# zumo_uni_i2c_01.net
KiCad netlist of a schematic drawn in EAGLE
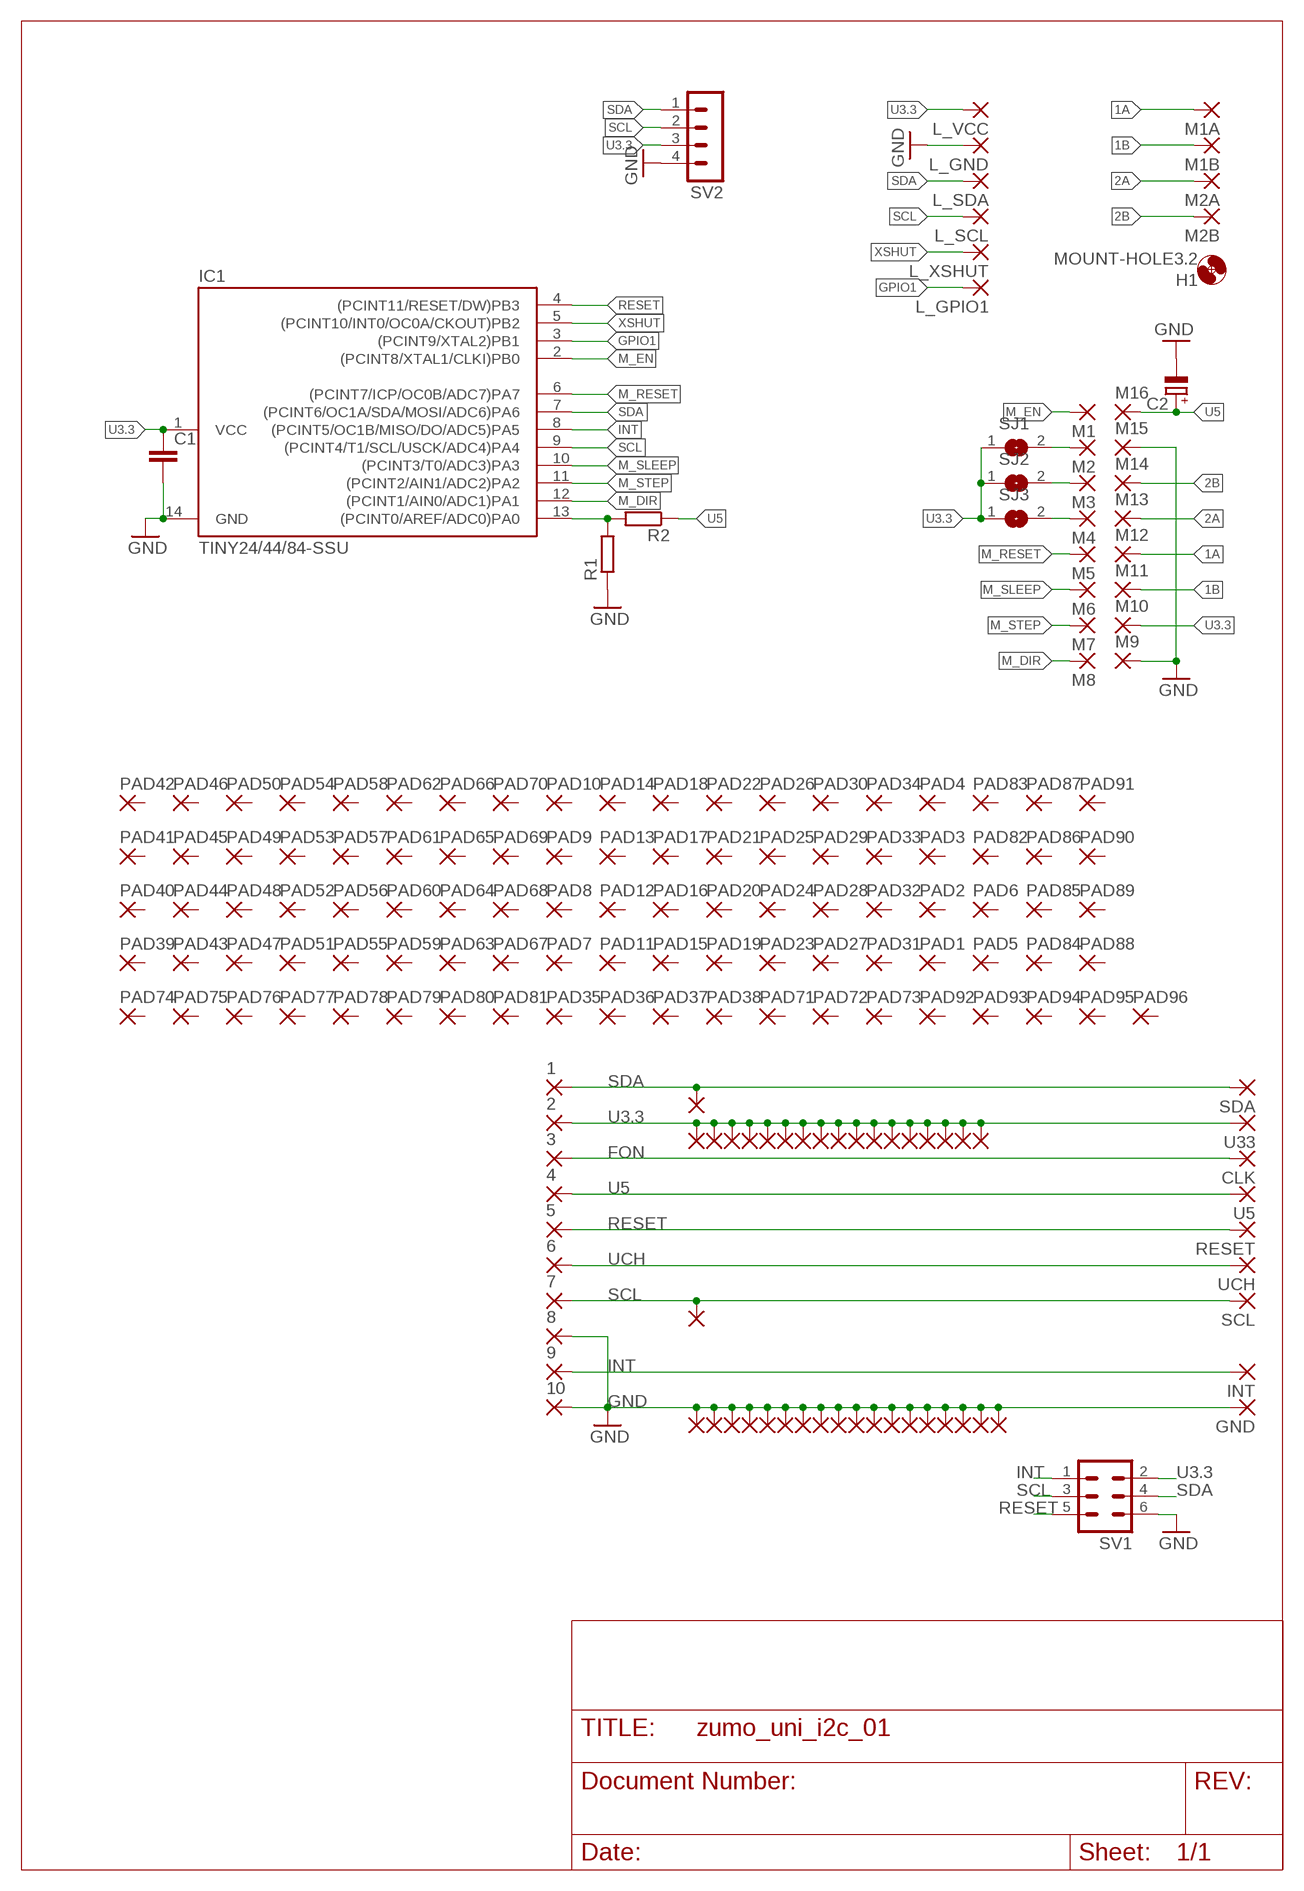
[diagram p0: schematic, sheet 1]

(export (version "E")
  (design (tool "Eeschema 10.0.6"))
  (components
    (comp (ref "1")
      (value "SMD2")
      (footprint "eagle-import:SMD1,27-2,54")
      (libsource (lib "eagle-import") (part "SMD2"))
    )
    (comp (ref "2")
      (value "SMD2")
      (footprint "eagle-import:SMD1,27-2,54")
      (libsource (lib "eagle-import") (part "SMD2"))
    )
    (comp (ref "3")
      (value "SMD2")
      (footprint "eagle-import:SMD1,27-2,54")
      (libsource (lib "eagle-import") (part "SMD2"))
    )
    (comp (ref "4")
      (value "SMD2")
      (footprint "eagle-import:SMD1,27-2,54")
      (libsource (lib "eagle-import") (part "SMD2"))
    )
    (comp (ref "5")
      (value "SMD2")
      (footprint "eagle-import:SMD1,27-2,54")
      (libsource (lib "eagle-import") (part "SMD2"))
    )
    (comp (ref "6")
      (value "SMD2")
      (footprint "eagle-import:SMD1,27-2,54")
      (libsource (lib "eagle-import") (part "SMD2"))
    )
    (comp (ref "7")
      (value "SMD2")
      (footprint "eagle-import:SMD1,27-2,54")
      (libsource (lib "eagle-import") (part "SMD2"))
    )
    (comp (ref "8")
      (value "SMD2")
      (footprint "eagle-import:SMD1,27-2,54")
      (libsource (lib "eagle-import") (part "SMD2"))
    )
    (comp (ref "9")
      (value "SMD2")
      (footprint "eagle-import:SMD1,27-2,54")
      (libsource (lib "eagle-import") (part "SMD2"))
    )
    (comp (ref "10")
      (value "SMD2")
      (footprint "eagle-import:SMD1,27-2,54")
      (libsource (lib "eagle-import") (part "SMD2"))
    )
    (comp (ref "C1")
      (value "C-EUC0805")
      (footprint "eagle-import:C0805")
      (libsource (lib "eagle-import") (part "C-EUC0805"))
    )
    (comp (ref "C2")
      (value "CPOL-EUSMCC")
      (footprint "eagle-import:SMC_C")
      (libsource (lib "eagle-import") (part "CPOL-EUSMCC"))
    )
    (comp (ref "CLK")
      (value "1,6/0,9")
      (footprint "eagle-import:1,6_0,9")
      (libsource (lib "eagle-import") (part "1,6/0,9"))
    )
    (comp (ref "GND")
      (value "1,6/0,9")
      (footprint "eagle-import:1,6_0,9")
      (libsource (lib "eagle-import") (part "1,6/0,9"))
    )
    (comp (ref "H1")
      (value "MOUNT-HOLE3.2")
      (footprint "eagle-import:3,2")
      (libsource (lib "eagle-import") (part "MOUNT-HOLE3.2"))
    )
    (comp (ref "IC1")
      (value "TINY24/44/84-SSU")
      (footprint "eagle-import:SOIC14")
      (libsource (lib "eagle-import") (part "TINY24/44/84-SSU"))
    )
    (comp (ref "INT")
      (value "1,6/0,9")
      (footprint "eagle-import:1,6_0,9")
      (libsource (lib "eagle-import") (part "1,6/0,9"))
    )
    (comp (ref "L_GND")
      (value "1,6/0,8")
      (footprint "eagle-import:1,6_0,8")
      (libsource (lib "eagle-import") (part "1,6/0,8"))
    )
    (comp (ref "L_GPIO1")
      (value "1,6/0,8")
      (footprint "eagle-import:1,6_0,8")
      (libsource (lib "eagle-import") (part "1,6/0,8"))
    )
    (comp (ref "L_SCL")
      (value "1,6/0,8")
      (footprint "eagle-import:1,6_0,8")
      (libsource (lib "eagle-import") (part "1,6/0,8"))
    )
    (comp (ref "L_SDA")
      (value "1,6/0,8")
      (footprint "eagle-import:1,6_0,8")
      (libsource (lib "eagle-import") (part "1,6/0,8"))
    )
    (comp (ref "L_VCC")
      (value "1,6/0,8")
      (footprint "eagle-import:1,6_0,8")
      (libsource (lib "eagle-import") (part "1,6/0,8"))
    )
    (comp (ref "L_XSHUT")
      (value "1,6/0,8")
      (footprint "eagle-import:1,6_0,8")
      (libsource (lib "eagle-import") (part "1,6/0,8"))
    )
    (comp (ref "M1")
      (value "1,6/0,9")
      (footprint "eagle-import:1,6_0,9")
      (libsource (lib "eagle-import") (part "1,6/0,9"))
    )
    (comp (ref "M1A")
      (value "1,6/0,8")
      (footprint "eagle-import:1,6_0,8")
      (libsource (lib "eagle-import") (part "1,6/0,8"))
    )
    (comp (ref "M1B")
      (value "1,6/0,8")
      (footprint "eagle-import:1,6_0,8")
      (libsource (lib "eagle-import") (part "1,6/0,8"))
    )
    (comp (ref "M2")
      (value "1,6/0,9")
      (footprint "eagle-import:1,6_0,9")
      (libsource (lib "eagle-import") (part "1,6/0,9"))
    )
    (comp (ref "M2A")
      (value "1,6/0,8")
      (footprint "eagle-import:1,6_0,8")
      (libsource (lib "eagle-import") (part "1,6/0,8"))
    )
    (comp (ref "M2B")
      (value "1,6/0,8")
      (footprint "eagle-import:1,6_0,8")
      (libsource (lib "eagle-import") (part "1,6/0,8"))
    )
    (comp (ref "M3")
      (value "1,6/0,9")
      (footprint "eagle-import:1,6_0,9")
      (libsource (lib "eagle-import") (part "1,6/0,9"))
    )
    (comp (ref "M4")
      (value "1,6/0,9")
      (footprint "eagle-import:1,6_0,9")
      (libsource (lib "eagle-import") (part "1,6/0,9"))
    )
    (comp (ref "M5")
      (value "1,6/0,9")
      (footprint "eagle-import:1,6_0,9")
      (libsource (lib "eagle-import") (part "1,6/0,9"))
    )
    (comp (ref "M6")
      (value "1,6/0,9")
      (footprint "eagle-import:1,6_0,9")
      (libsource (lib "eagle-import") (part "1,6/0,9"))
    )
    (comp (ref "M7")
      (value "1,6/0,9")
      (footprint "eagle-import:1,6_0,9")
      (libsource (lib "eagle-import") (part "1,6/0,9"))
    )
    (comp (ref "M8")
      (value "1,6/0,9")
      (footprint "eagle-import:1,6_0,9")
      (libsource (lib "eagle-import") (part "1,6/0,9"))
    )
    (comp (ref "M9")
      (value "1,6/0,9")
      (footprint "eagle-import:1,6_0,9")
      (libsource (lib "eagle-import") (part "1,6/0,9"))
    )
    (comp (ref "M10")
      (value "1,6/0,9")
      (footprint "eagle-import:1,6_0,9")
      (libsource (lib "eagle-import") (part "1,6/0,9"))
    )
    (comp (ref "M11")
      (value "1,6/0,9")
      (footprint "eagle-import:1,6_0,9")
      (libsource (lib "eagle-import") (part "1,6/0,9"))
    )
    (comp (ref "M12")
      (value "1,6/0,9")
      (footprint "eagle-import:1,6_0,9")
      (libsource (lib "eagle-import") (part "1,6/0,9"))
    )
    (comp (ref "M13")
      (value "1,6/0,9")
      (footprint "eagle-import:1,6_0,9")
      (libsource (lib "eagle-import") (part "1,6/0,9"))
    )
    (comp (ref "M14")
      (value "1,6/0,9")
      (footprint "eagle-import:1,6_0,9")
      (libsource (lib "eagle-import") (part "1,6/0,9"))
    )
    (comp (ref "M15")
      (value "1,6/0,9")
      (footprint "eagle-import:1,6_0,9")
      (libsource (lib "eagle-import") (part "1,6/0,9"))
    )
    (comp (ref "M16")
      (value "1,6/0,9")
      (footprint "eagle-import:1,6_0,9")
      (libsource (lib "eagle-import") (part "1,6/0,9"))
    )
    (comp (ref "MISO1")
      (value "1,6/0,9")
      (footprint "eagle-import:1,6_0,9")
      (libsource (lib "eagle-import") (part "1,6/0,9"))
    )
    (comp (ref "MISO4")
      (value "1,6/0,9")
      (footprint "eagle-import:1,6_0,9")
      (libsource (lib "eagle-import") (part "1,6/0,9"))
    )
    (comp (ref "MISO5")
      (value "1,6/0,9")
      (footprint "eagle-import:1,6_0,9")
      (libsource (lib "eagle-import") (part "1,6/0,9"))
    )
    (comp (ref "MISO6")
      (value "1,6/0,9")
      (footprint "eagle-import:1,6_0,9")
      (libsource (lib "eagle-import") (part "1,6/0,9"))
    )
    (comp (ref "MISO7")
      (value "1,6/0,9")
      (footprint "eagle-import:1,6_0,9")
      (libsource (lib "eagle-import") (part "1,6/0,9"))
    )
    (comp (ref "MISO8")
      (value "1,6/0,9")
      (footprint "eagle-import:1,6_0,9")
      (libsource (lib "eagle-import") (part "1,6/0,9"))
    )
    (comp (ref "MISO9")
      (value "1,6/0,9")
      (footprint "eagle-import:1,6_0,9")
      (libsource (lib "eagle-import") (part "1,6/0,9"))
    )
    (comp (ref "MISO10")
      (value "1,6/0,9")
      (footprint "eagle-import:1,6_0,9")
      (libsource (lib "eagle-import") (part "1,6/0,9"))
    )
    (comp (ref "MISO11")
      (value "1,6/0,9")
      (footprint "eagle-import:1,6_0,9")
      (libsource (lib "eagle-import") (part "1,6/0,9"))
    )
    (comp (ref "MISO12")
      (value "1,6/0,9")
      (footprint "eagle-import:1,6_0,9")
      (libsource (lib "eagle-import") (part "1,6/0,9"))
    )
    (comp (ref "MISO13")
      (value "1,6/0,9")
      (footprint "eagle-import:1,6_0,9")
      (libsource (lib "eagle-import") (part "1,6/0,9"))
    )
    (comp (ref "MISO14")
      (value "1,6/0,9")
      (footprint "eagle-import:1,6_0,9")
      (libsource (lib "eagle-import") (part "1,6/0,9"))
    )
    (comp (ref "MISO15")
      (value "1,6/0,9")
      (footprint "eagle-import:1,6_0,9")
      (libsource (lib "eagle-import") (part "1,6/0,9"))
    )
    (comp (ref "MISO16")
      (value "1,6/0,9")
      (footprint "eagle-import:1,6_0,9")
      (libsource (lib "eagle-import") (part "1,6/0,9"))
    )
    (comp (ref "MISO17")
      (value "1,6/0,9")
      (footprint "eagle-import:1,6_0,9")
      (libsource (lib "eagle-import") (part "1,6/0,9"))
    )
    (comp (ref "MISO18")
      (value "1,6/0,9")
      (footprint "eagle-import:1,6_0,9")
      (libsource (lib "eagle-import") (part "1,6/0,9"))
    )
    (comp (ref "MISO19")
      (value "1,6/0,9")
      (footprint "eagle-import:1,6_0,9")
      (libsource (lib "eagle-import") (part "1,6/0,9"))
    )
    (comp (ref "MISO20")
      (value "1,6/0,9")
      (footprint "eagle-import:1,6_0,9")
      (libsource (lib "eagle-import") (part "1,6/0,9"))
    )
    (comp (ref "MISO21")
      (value "1,6/0,9")
      (footprint "eagle-import:1,6_0,9")
      (libsource (lib "eagle-import") (part "1,6/0,9"))
    )
    (comp (ref "MISO22")
      (value "1,6/0,9")
      (footprint "eagle-import:1,6_0,9")
      (libsource (lib "eagle-import") (part "1,6/0,9"))
    )
    (comp (ref "MISO23")
      (value "1,6/0,9")
      (footprint "eagle-import:1,6_0,9")
      (libsource (lib "eagle-import") (part "1,6/0,9"))
    )
    (comp (ref "MISO24")
      (value "1,6/0,9")
      (footprint "eagle-import:1,6_0,9")
      (libsource (lib "eagle-import") (part "1,6/0,9"))
    )
    (comp (ref "MISO25")
      (value "1,6/0,9")
      (footprint "eagle-import:1,6_0,9")
      (libsource (lib "eagle-import") (part "1,6/0,9"))
    )
    (comp (ref "MISO26")
      (value "1,6/0,9")
      (footprint "eagle-import:1,6_0,9")
      (libsource (lib "eagle-import") (part "1,6/0,9"))
    )
    (comp (ref "MISO27")
      (value "1,6/0,9")
      (footprint "eagle-import:1,6_0,9")
      (libsource (lib "eagle-import") (part "1,6/0,9"))
    )
    (comp (ref "MISO28")
      (value "1,6/0,9")
      (footprint "eagle-import:1,6_0,9")
      (libsource (lib "eagle-import") (part "1,6/0,9"))
    )
    (comp (ref "MISO29")
      (value "1,6/0,9")
      (footprint "eagle-import:1,6_0,9")
      (libsource (lib "eagle-import") (part "1,6/0,9"))
    )
    (comp (ref "MISO30")
      (value "1,6/0,9")
      (footprint "eagle-import:1,6_0,9")
      (libsource (lib "eagle-import") (part "1,6/0,9"))
    )
    (comp (ref "MISO31")
      (value "1,6/0,9")
      (footprint "eagle-import:1,6_0,9")
      (libsource (lib "eagle-import") (part "1,6/0,9"))
    )
    (comp (ref "MISO32")
      (value "1,6/0,9")
      (footprint "eagle-import:1,6_0,9")
      (libsource (lib "eagle-import") (part "1,6/0,9"))
    )
    (comp (ref "MISO33")
      (value "1,6/0,9")
      (footprint "eagle-import:1,6_0,9")
      (libsource (lib "eagle-import") (part "1,6/0,9"))
    )
    (comp (ref "MISO34")
      (value "1,6/0,9")
      (footprint "eagle-import:1,6_0,9")
      (libsource (lib "eagle-import") (part "1,6/0,9"))
    )
    (comp (ref "MISO35")
      (value "1,6/0,9")
      (footprint "eagle-import:1,6_0,9")
      (libsource (lib "eagle-import") (part "1,6/0,9"))
    )
    (comp (ref "MISO36")
      (value "1,6/0,9")
      (footprint "eagle-import:1,6_0,9")
      (libsource (lib "eagle-import") (part "1,6/0,9"))
    )
    (comp (ref "MISO37")
      (value "1,6/0,9")
      (footprint "eagle-import:1,6_0,9")
      (libsource (lib "eagle-import") (part "1,6/0,9"))
    )
    (comp (ref "MISO41")
      (value "1,6/0,9")
      (footprint "eagle-import:1,6_0,9")
      (libsource (lib "eagle-import") (part "1,6/0,9"))
    )
    (comp (ref "MISO43")
      (value "1,6/0,9")
      (footprint "eagle-import:1,6_0,9")
      (libsource (lib "eagle-import") (part "1,6/0,9"))
    )
    (comp (ref "PAD1")
      (value "1,6/0,9")
      (footprint "eagle-import:1,6_0,9")
      (libsource (lib "eagle-import") (part "1,6/0,9"))
    )
    (comp (ref "PAD2")
      (value "1,6/0,9")
      (footprint "eagle-import:1,6_0,9")
      (libsource (lib "eagle-import") (part "1,6/0,9"))
    )
    (comp (ref "PAD3")
      (value "1,6/0,9")
      (footprint "eagle-import:1,6_0,9")
      (libsource (lib "eagle-import") (part "1,6/0,9"))
    )
    (comp (ref "PAD4")
      (value "1,6/0,9")
      (footprint "eagle-import:1,6_0,9")
      (libsource (lib "eagle-import") (part "1,6/0,9"))
    )
    (comp (ref "PAD5")
      (value "1,6/0,9")
      (footprint "eagle-import:1,6_0,9")
      (libsource (lib "eagle-import") (part "1,6/0,9"))
    )
    (comp (ref "PAD6")
      (value "1,6/0,9")
      (footprint "eagle-import:1,6_0,9")
      (libsource (lib "eagle-import") (part "1,6/0,9"))
    )
    (comp (ref "PAD7")
      (value "1,6/0,9")
      (footprint "eagle-import:1,6_0,9")
      (libsource (lib "eagle-import") (part "1,6/0,9"))
    )
    (comp (ref "PAD8")
      (value "1,6/0,9")
      (footprint "eagle-import:1,6_0,9")
      (libsource (lib "eagle-import") (part "1,6/0,9"))
    )
    (comp (ref "PAD9")
      (value "1,6/0,9")
      (footprint "eagle-import:1,6_0,9")
      (libsource (lib "eagle-import") (part "1,6/0,9"))
    )
    (comp (ref "PAD10")
      (value "1,6/0,9")
      (footprint "eagle-import:1,6_0,9")
      (libsource (lib "eagle-import") (part "1,6/0,9"))
    )
    (comp (ref "PAD11")
      (value "1,6/0,9")
      (footprint "eagle-import:1,6_0,9")
      (libsource (lib "eagle-import") (part "1,6/0,9"))
    )
    (comp (ref "PAD12")
      (value "1,6/0,9")
      (footprint "eagle-import:1,6_0,9")
      (libsource (lib "eagle-import") (part "1,6/0,9"))
    )
    (comp (ref "PAD13")
      (value "1,6/0,9")
      (footprint "eagle-import:1,6_0,9")
      (libsource (lib "eagle-import") (part "1,6/0,9"))
    )
    (comp (ref "PAD14")
      (value "1,6/0,9")
      (footprint "eagle-import:1,6_0,9")
      (libsource (lib "eagle-import") (part "1,6/0,9"))
    )
    (comp (ref "PAD15")
      (value "1,6/0,9")
      (footprint "eagle-import:1,6_0,9")
      (libsource (lib "eagle-import") (part "1,6/0,9"))
    )
    (comp (ref "PAD16")
      (value "1,6/0,9")
      (footprint "eagle-import:1,6_0,9")
      (libsource (lib "eagle-import") (part "1,6/0,9"))
    )
    (comp (ref "PAD17")
      (value "1,6/0,9")
      (footprint "eagle-import:1,6_0,9")
      (libsource (lib "eagle-import") (part "1,6/0,9"))
    )
    (comp (ref "PAD18")
      (value "1,6/0,9")
      (footprint "eagle-import:1,6_0,9")
      (libsource (lib "eagle-import") (part "1,6/0,9"))
    )
    (comp (ref "PAD19")
      (value "1,6/0,9")
      (footprint "eagle-import:1,6_0,9")
      (libsource (lib "eagle-import") (part "1,6/0,9"))
    )
    (comp (ref "PAD20")
      (value "1,6/0,9")
      (footprint "eagle-import:1,6_0,9")
      (libsource (lib "eagle-import") (part "1,6/0,9"))
    )
    (comp (ref "PAD21")
      (value "1,6/0,9")
      (footprint "eagle-import:1,6_0,9")
      (libsource (lib "eagle-import") (part "1,6/0,9"))
    )
    (comp (ref "PAD22")
      (value "1,6/0,9")
      (footprint "eagle-import:1,6_0,9")
      (libsource (lib "eagle-import") (part "1,6/0,9"))
    )
    (comp (ref "PAD23")
      (value "1,6/0,9")
      (footprint "eagle-import:1,6_0,9")
      (libsource (lib "eagle-import") (part "1,6/0,9"))
    )
    (comp (ref "PAD24")
      (value "1,6/0,9")
      (footprint "eagle-import:1,6_0,9")
      (libsource (lib "eagle-import") (part "1,6/0,9"))
    )
    (comp (ref "PAD25")
      (value "1,6/0,9")
      (footprint "eagle-import:1,6_0,9")
      (libsource (lib "eagle-import") (part "1,6/0,9"))
    )
    (comp (ref "PAD26")
      (value "1,6/0,9")
      (footprint "eagle-import:1,6_0,9")
      (libsource (lib "eagle-import") (part "1,6/0,9"))
    )
    (comp (ref "PAD27")
      (value "1,6/0,9")
      (footprint "eagle-import:1,6_0,9")
      (libsource (lib "eagle-import") (part "1,6/0,9"))
    )
    (comp (ref "PAD28")
      (value "1,6/0,9")
      (footprint "eagle-import:1,6_0,9")
      (libsource (lib "eagle-import") (part "1,6/0,9"))
    )
    (comp (ref "PAD29")
      (value "1,6/0,9")
      (footprint "eagle-import:1,6_0,9")
      (libsource (lib "eagle-import") (part "1,6/0,9"))
    )
    (comp (ref "PAD30")
      (value "1,6/0,9")
      (footprint "eagle-import:1,6_0,9")
      (libsource (lib "eagle-import") (part "1,6/0,9"))
    )
    (comp (ref "PAD31")
      (value "1,6/0,9")
      (footprint "eagle-import:1,6_0,9")
      (libsource (lib "eagle-import") (part "1,6/0,9"))
    )
    (comp (ref "PAD32")
      (value "1,6/0,9")
      (footprint "eagle-import:1,6_0,9")
      (libsource (lib "eagle-import") (part "1,6/0,9"))
    )
    (comp (ref "PAD33")
      (value "1,6/0,9")
      (footprint "eagle-import:1,6_0,9")
      (libsource (lib "eagle-import") (part "1,6/0,9"))
    )
    (comp (ref "PAD34")
      (value "1,6/0,9")
      (footprint "eagle-import:1,6_0,9")
      (libsource (lib "eagle-import") (part "1,6/0,9"))
    )
    (comp (ref "PAD35")
      (value "1,6/0,9")
      (footprint "eagle-import:1,6_0,9")
      (libsource (lib "eagle-import") (part "1,6/0,9"))
    )
    (comp (ref "PAD36")
      (value "1,6/0,9")
      (footprint "eagle-import:1,6_0,9")
      (libsource (lib "eagle-import") (part "1,6/0,9"))
    )
    (comp (ref "PAD37")
      (value "1,6/0,9")
      (footprint "eagle-import:1,6_0,9")
      (libsource (lib "eagle-import") (part "1,6/0,9"))
    )
    (comp (ref "PAD38")
      (value "1,6/0,9")
      (footprint "eagle-import:1,6_0,9")
      (libsource (lib "eagle-import") (part "1,6/0,9"))
    )
    (comp (ref "PAD39")
      (value "1,6/0,9")
      (footprint "eagle-import:1,6_0,9")
      (libsource (lib "eagle-import") (part "1,6/0,9"))
    )
    (comp (ref "PAD40")
      (value "1,6/0,9")
      (footprint "eagle-import:1,6_0,9")
      (libsource (lib "eagle-import") (part "1,6/0,9"))
    )
    (comp (ref "PAD41")
      (value "1,6/0,9")
      (footprint "eagle-import:1,6_0,9")
      (libsource (lib "eagle-import") (part "1,6/0,9"))
    )
    (comp (ref "PAD42")
      (value "1,6/0,9")
      (footprint "eagle-import:1,6_0,9")
      (libsource (lib "eagle-import") (part "1,6/0,9"))
    )
    (comp (ref "PAD43")
      (value "1,6/0,9")
      (footprint "eagle-import:1,6_0,9")
      (libsource (lib "eagle-import") (part "1,6/0,9"))
    )
    (comp (ref "PAD44")
      (value "1,6/0,9")
      (footprint "eagle-import:1,6_0,9")
      (libsource (lib "eagle-import") (part "1,6/0,9"))
    )
    (comp (ref "PAD45")
      (value "1,6/0,9")
      (footprint "eagle-import:1,6_0,9")
      (libsource (lib "eagle-import") (part "1,6/0,9"))
    )
    (comp (ref "PAD46")
      (value "1,6/0,9")
      (footprint "eagle-import:1,6_0,9")
      (libsource (lib "eagle-import") (part "1,6/0,9"))
    )
    (comp (ref "PAD47")
      (value "1,6/0,9")
      (footprint "eagle-import:1,6_0,9")
      (libsource (lib "eagle-import") (part "1,6/0,9"))
    )
    (comp (ref "PAD48")
      (value "1,6/0,9")
      (footprint "eagle-import:1,6_0,9")
      (libsource (lib "eagle-import") (part "1,6/0,9"))
    )
    (comp (ref "PAD49")
      (value "1,6/0,9")
      (footprint "eagle-import:1,6_0,9")
      (libsource (lib "eagle-import") (part "1,6/0,9"))
    )
    (comp (ref "PAD50")
      (value "1,6/0,9")
      (footprint "eagle-import:1,6_0,9")
      (libsource (lib "eagle-import") (part "1,6/0,9"))
    )
    (comp (ref "PAD51")
      (value "1,6/0,9")
      (footprint "eagle-import:1,6_0,9")
      (libsource (lib "eagle-import") (part "1,6/0,9"))
    )
    (comp (ref "PAD52")
      (value "1,6/0,9")
      (footprint "eagle-import:1,6_0,9")
      (libsource (lib "eagle-import") (part "1,6/0,9"))
    )
    (comp (ref "PAD53")
      (value "1,6/0,9")
      (footprint "eagle-import:1,6_0,9")
      (libsource (lib "eagle-import") (part "1,6/0,9"))
    )
    (comp (ref "PAD54")
      (value "1,6/0,9")
      (footprint "eagle-import:1,6_0,9")
      (libsource (lib "eagle-import") (part "1,6/0,9"))
    )
    (comp (ref "PAD55")
      (value "1,6/0,9")
      (footprint "eagle-import:1,6_0,9")
      (libsource (lib "eagle-import") (part "1,6/0,9"))
    )
    (comp (ref "PAD56")
      (value "1,6/0,9")
      (footprint "eagle-import:1,6_0,9")
      (libsource (lib "eagle-import") (part "1,6/0,9"))
    )
    (comp (ref "PAD57")
      (value "1,6/0,9")
      (footprint "eagle-import:1,6_0,9")
      (libsource (lib "eagle-import") (part "1,6/0,9"))
    )
    (comp (ref "PAD58")
      (value "1,6/0,9")
      (footprint "eagle-import:1,6_0,9")
      (libsource (lib "eagle-import") (part "1,6/0,9"))
    )
    (comp (ref "PAD59")
      (value "1,6/0,9")
      (footprint "eagle-import:1,6_0,9")
      (libsource (lib "eagle-import") (part "1,6/0,9"))
    )
    (comp (ref "PAD60")
      (value "1,6/0,9")
      (footprint "eagle-import:1,6_0,9")
      (libsource (lib "eagle-import") (part "1,6/0,9"))
    )
    (comp (ref "PAD61")
      (value "1,6/0,9")
      (footprint "eagle-import:1,6_0,9")
      (libsource (lib "eagle-import") (part "1,6/0,9"))
    )
    (comp (ref "PAD62")
      (value "1,6/0,9")
      (footprint "eagle-import:1,6_0,9")
      (libsource (lib "eagle-import") (part "1,6/0,9"))
    )
    (comp (ref "PAD63")
      (value "1,6/0,9")
      (footprint "eagle-import:1,6_0,9")
      (libsource (lib "eagle-import") (part "1,6/0,9"))
    )
    (comp (ref "PAD64")
      (value "1,6/0,9")
      (footprint "eagle-import:1,6_0,9")
      (libsource (lib "eagle-import") (part "1,6/0,9"))
    )
    (comp (ref "PAD65")
      (value "1,6/0,9")
      (footprint "eagle-import:1,6_0,9")
      (libsource (lib "eagle-import") (part "1,6/0,9"))
    )
    (comp (ref "PAD66")
      (value "1,6/0,9")
      (footprint "eagle-import:1,6_0,9")
      (libsource (lib "eagle-import") (part "1,6/0,9"))
    )
    (comp (ref "PAD67")
      (value "1,6/0,9")
      (footprint "eagle-import:1,6_0,9")
      (libsource (lib "eagle-import") (part "1,6/0,9"))
    )
    (comp (ref "PAD68")
      (value "1,6/0,9")
      (footprint "eagle-import:1,6_0,9")
      (libsource (lib "eagle-import") (part "1,6/0,9"))
    )
    (comp (ref "PAD69")
      (value "1,6/0,9")
      (footprint "eagle-import:1,6_0,9")
      (libsource (lib "eagle-import") (part "1,6/0,9"))
    )
    (comp (ref "PAD70")
      (value "1,6/0,9")
      (footprint "eagle-import:1,6_0,9")
      (libsource (lib "eagle-import") (part "1,6/0,9"))
    )
    (comp (ref "PAD71")
      (value "1,6/0,9")
      (footprint "eagle-import:1,6_0,9")
      (libsource (lib "eagle-import") (part "1,6/0,9"))
    )
    (comp (ref "PAD72")
      (value "1,6/0,9")
      (footprint "eagle-import:1,6_0,9")
      (libsource (lib "eagle-import") (part "1,6/0,9"))
    )
    (comp (ref "PAD73")
      (value "1,6/0,9")
      (footprint "eagle-import:1,6_0,9")
      (libsource (lib "eagle-import") (part "1,6/0,9"))
    )
    (comp (ref "PAD74")
      (value "1,6/0,9")
      (footprint "eagle-import:1,6_0,9")
      (libsource (lib "eagle-import") (part "1,6/0,9"))
    )
    (comp (ref "PAD75")
      (value "1,6/0,9")
      (footprint "eagle-import:1,6_0,9")
      (libsource (lib "eagle-import") (part "1,6/0,9"))
    )
    (comp (ref "PAD76")
      (value "1,6/0,9")
      (footprint "eagle-import:1,6_0,9")
      (libsource (lib "eagle-import") (part "1,6/0,9"))
    )
    (comp (ref "PAD77")
      (value "1,6/0,9")
      (footprint "eagle-import:1,6_0,9")
      (libsource (lib "eagle-import") (part "1,6/0,9"))
    )
    (comp (ref "PAD78")
      (value "1,6/0,9")
      (footprint "eagle-import:1,6_0,9")
      (libsource (lib "eagle-import") (part "1,6/0,9"))
    )
    (comp (ref "PAD79")
      (value "1,6/0,9")
      (footprint "eagle-import:1,6_0,9")
      (libsource (lib "eagle-import") (part "1,6/0,9"))
    )
    (comp (ref "PAD80")
      (value "1,6/0,9")
      (footprint "eagle-import:1,6_0,9")
      (libsource (lib "eagle-import") (part "1,6/0,9"))
    )
    (comp (ref "PAD81")
      (value "1,6/0,9")
      (footprint "eagle-import:1,6_0,9")
      (libsource (lib "eagle-import") (part "1,6/0,9"))
    )
    (comp (ref "PAD82")
      (value "1,6/0,9")
      (footprint "eagle-import:1,6_0,9")
      (libsource (lib "eagle-import") (part "1,6/0,9"))
    )
    (comp (ref "PAD83")
      (value "1,6/0,9")
      (footprint "eagle-import:1,6_0,9")
      (libsource (lib "eagle-import") (part "1,6/0,9"))
    )
    (comp (ref "PAD84")
      (value "1,6/0,9")
      (footprint "eagle-import:1,6_0,9")
      (libsource (lib "eagle-import") (part "1,6/0,9"))
    )
    (comp (ref "PAD85")
      (value "1,6/0,9")
      (footprint "eagle-import:1,6_0,9")
      (libsource (lib "eagle-import") (part "1,6/0,9"))
    )
    (comp (ref "PAD86")
      (value "1,6/0,9")
      (footprint "eagle-import:1,6_0,9")
      (libsource (lib "eagle-import") (part "1,6/0,9"))
    )
    (comp (ref "PAD87")
      (value "1,6/0,9")
      (footprint "eagle-import:1,6_0,9")
      (libsource (lib "eagle-import") (part "1,6/0,9"))
    )
    (comp (ref "PAD88")
      (value "1,6/0,9")
      (footprint "eagle-import:1,6_0,9")
      (libsource (lib "eagle-import") (part "1,6/0,9"))
    )
    (comp (ref "PAD89")
      (value "1,6/0,9")
      (footprint "eagle-import:1,6_0,9")
      (libsource (lib "eagle-import") (part "1,6/0,9"))
    )
    (comp (ref "PAD90")
      (value "1,6/0,9")
      (footprint "eagle-import:1,6_0,9")
      (libsource (lib "eagle-import") (part "1,6/0,9"))
    )
    (comp (ref "PAD91")
      (value "1,6/0,9")
      (footprint "eagle-import:1,6_0,9")
      (libsource (lib "eagle-import") (part "1,6/0,9"))
    )
    (comp (ref "PAD92")
      (value "1,6/0,9")
      (footprint "eagle-import:1,6_0,9")
      (libsource (lib "eagle-import") (part "1,6/0,9"))
    )
    (comp (ref "PAD93")
      (value "1,6/0,9")
      (footprint "eagle-import:1,6_0,9")
      (libsource (lib "eagle-import") (part "1,6/0,9"))
    )
    (comp (ref "PAD94")
      (value "1,6/0,9")
      (footprint "eagle-import:1,6_0,9")
      (libsource (lib "eagle-import") (part "1,6/0,9"))
    )
    (comp (ref "PAD95")
      (value "1,6/0,9")
      (footprint "eagle-import:1,6_0,9")
      (libsource (lib "eagle-import") (part "1,6/0,9"))
    )
    (comp (ref "PAD96")
      (value "1,6/0,9")
      (footprint "eagle-import:1,6_0,9")
      (libsource (lib "eagle-import") (part "1,6/0,9"))
    )
    (comp (ref "R1")
      (value "R-EU_M0805")
      (footprint "eagle-import:M0805")
      (libsource (lib "eagle-import") (part "R-EU_M0805"))
    )
    (comp (ref "R2")
      (value "R-EU_M0805")
      (footprint "eagle-import:M0805")
      (libsource (lib "eagle-import") (part "R-EU_M0805"))
    )
    (comp (ref "RESET")
      (value "1,6/0,9")
      (footprint "eagle-import:1,6_0,9")
      (libsource (lib "eagle-import") (part "1,6/0,9"))
    )
    (comp (ref "SCL")
      (value "1,6/0,9")
      (footprint "eagle-import:1,6_0,9")
      (libsource (lib "eagle-import") (part "1,6/0,9"))
    )
    (comp (ref "SDA")
      (value "1,6/0,9")
      (footprint "eagle-import:1,6_0,9")
      (libsource (lib "eagle-import") (part "1,6/0,9"))
    )
    (comp (ref "SJ1") (value "SJ") (footprint "eagle-import:SJ") (libsource (lib "eagle-import") (part "SJ")))
    (comp (ref "SJ2") (value "SJ") (footprint "eagle-import:SJ") (libsource (lib "eagle-import") (part "SJ")))
    (comp (ref "SJ3") (value "SJ") (footprint "eagle-import:SJ") (libsource (lib "eagle-import") (part "SJ")))
    (comp (ref "SV1")
      (value "ML6")
      (footprint "eagle-import:ML6")
      (libsource (lib "eagle-import") (part "ML6"))
    )
    (comp (ref "SV2")
      (value "MA04-1")
      (footprint "eagle-import:MA04-1")
      (libsource (lib "eagle-import") (part "MA04-1"))
    )
    (comp (ref "U5")
      (value "1,6/0,9")
      (footprint "eagle-import:1,6_0,9")
      (libsource (lib "eagle-import") (part "1,6/0,9"))
    )
    (comp (ref "U33")
      (value "1,6/0,9")
      (footprint "eagle-import:1,6_0,9")
      (libsource (lib "eagle-import") (part "1,6/0,9"))
    )
    (comp (ref "UCH")
      (value "1,6/0,9")
      (footprint "eagle-import:1,6_0,9")
      (libsource (lib "eagle-import") (part "1,6/0,9"))
    )
  )
  (nets
    (net (code "1") (name "/FON") (class "Default")
      (node (ref "3") (pin "1") (pinfunction "P_1") (pintype "passive"))
      (node (ref "CLK") (pin "1") (pinfunction "P_1") (pintype "passive"))
    )
    (net (code "2") (name "/UCH") (class "Default")
      (node (ref "6") (pin "1") (pinfunction "P_1") (pintype "passive"))
      (node (ref "UCH") (pin "1") (pinfunction "P_1") (pintype "passive"))
    )
    (net (code "3") (name "1A") (class "Default")
      (node (ref "M12") (pin "1") (pinfunction "P_1") (pintype "passive"))
      (node (ref "M1A") (pin "1") (pinfunction "P_1") (pintype "passive"))
    )
    (net (code "4") (name "1B") (class "Default")
      (node (ref "M11") (pin "1") (pinfunction "P_1") (pintype "passive"))
      (node (ref "M1B") (pin "1") (pinfunction "P_1") (pintype "passive"))
    )
    (net (code "5") (name "2A") (class "Default")
      (node (ref "M13") (pin "1") (pinfunction "P_1") (pintype "passive"))
      (node (ref "M2A") (pin "1") (pinfunction "P_1") (pintype "passive"))
    )
    (net (code "6") (name "2B") (class "Default")
      (node (ref "M14") (pin "1") (pinfunction "P_1") (pintype "passive"))
      (node (ref "M2B") (pin "1") (pinfunction "P_1") (pintype "passive"))
    )
    (net (code "7") (name "GND") (class "Default")
      (node (ref "10") (pin "1") (pinfunction "P_1") (pintype "passive"))
      (node (ref "8") (pin "1") (pinfunction "P_1") (pintype "passive"))
      (node (ref "C1") (pin "2") (pinfunction "2_2") (pintype "passive"))
      (node (ref "C2") (pin "-") (pinfunction "-_-") (pintype "passive"))
      (node (ref "GND") (pin "1") (pinfunction "P_1") (pintype "passive"))
      (node (ref "IC1") (pin "14") (pinfunction "GND_14") (pintype "power_in"))
      (node (ref "L_GND") (pin "1") (pinfunction "P_1") (pintype "passive"))
      (node (ref "M15") (pin "1") (pinfunction "P_1") (pintype "passive"))
      (node (ref "M9") (pin "1") (pinfunction "P_1") (pintype "passive"))
      (node (ref "MISO1") (pin "1") (pinfunction "P_1") (pintype "passive"))
      (node (ref "MISO10") (pin "1") (pinfunction "P_1") (pintype "passive"))
      (node (ref "MISO11") (pin "1") (pinfunction "P_1") (pintype "passive"))
      (node (ref "MISO12") (pin "1") (pinfunction "P_1") (pintype "passive"))
      (node (ref "MISO13") (pin "1") (pinfunction "P_1") (pintype "passive"))
      (node (ref "MISO14") (pin "1") (pinfunction "P_1") (pintype "passive"))
      (node (ref "MISO15") (pin "1") (pinfunction "P_1") (pintype "passive"))
      (node (ref "MISO16") (pin "1") (pinfunction "P_1") (pintype "passive"))
      (node (ref "MISO17") (pin "1") (pinfunction "P_1") (pintype "passive"))
      (node (ref "MISO18") (pin "1") (pinfunction "P_1") (pintype "passive"))
      (node (ref "MISO19") (pin "1") (pinfunction "P_1") (pintype "passive"))
      (node (ref "MISO20") (pin "1") (pinfunction "P_1") (pintype "passive"))
      (node (ref "MISO43") (pin "1") (pinfunction "P_1") (pintype "passive"))
      (node (ref "MISO5") (pin "1") (pinfunction "P_1") (pintype "passive"))
      (node (ref "MISO6") (pin "1") (pinfunction "P_1") (pintype "passive"))
      (node (ref "MISO7") (pin "1") (pinfunction "P_1") (pintype "passive"))
      (node (ref "MISO8") (pin "1") (pinfunction "P_1") (pintype "passive"))
      (node (ref "MISO9") (pin "1") (pinfunction "P_1") (pintype "passive"))
      (node (ref "R1") (pin "1") (pinfunction "1_1") (pintype "passive"))
      (node (ref "SV1") (pin "6") (pinfunction "6_6") (pintype "passive"))
      (node (ref "SV2") (pin "4") (pinfunction "4_4") (pintype "passive"))
    )
    (net (code "8") (name "GPIO1") (class "Default")
      (node (ref "IC1") (pin "3") (pinfunction "(PCINT9/XTAL2)PB1_3") (pintype "bidirectional"))
      (node (ref "L_GPIO1") (pin "1") (pinfunction "P_1") (pintype "passive"))
    )
    (net (code "9") (name "INT") (class "Default")
      (node (ref "9") (pin "1") (pinfunction "P_1") (pintype "passive"))
      (node (ref "IC1") (pin "8") (pinfunction "(PCINT5/OC1B/MISO/DO/ADC5)PA5_8") (pintype "bidirectional"))
      (node (ref "INT") (pin "1") (pinfunction "P_1") (pintype "passive"))
      (node (ref "SV1") (pin "1") (pinfunction "1_1") (pintype "passive"))
    )
    (net (code "10") (name "M_DIR") (class "Default")
      (node (ref "IC1") (pin "12") (pinfunction "(PCINT1/AIN0/ADC1)PA1_12") (pintype "bidirectional"))
      (node (ref "M8") (pin "1") (pinfunction "P_1") (pintype "passive"))
    )
    (net (code "11") (name "M_EN") (class "Default")
      (node (ref "IC1") (pin "2") (pinfunction "(PCINT8/XTAL1/CLKI)PB0_2") (pintype "bidirectional"))
      (node (ref "M1") (pin "1") (pinfunction "P_1") (pintype "passive"))
    )
    (net (code "12") (name "M_RESET") (class "Default")
      (node (ref "IC1") (pin "6") (pinfunction "(PCINT7/ICP/OC0B/ADC7)PA7_6") (pintype "bidirectional"))
      (node (ref "M5") (pin "1") (pinfunction "P_1") (pintype "passive"))
    )
    (net (code "13") (name "M_SLEEP") (class "Default")
      (node (ref "IC1") (pin "10") (pinfunction "(PCINT3/T0/ADC3)PA3_10") (pintype "bidirectional"))
      (node (ref "M6") (pin "1") (pinfunction "P_1") (pintype "passive"))
    )
    (net (code "14") (name "M_STEP") (class "Default")
      (node (ref "IC1") (pin "11") (pinfunction "(PCINT2/AIN1/ADC2)PA2_11") (pintype "bidirectional"))
      (node (ref "M7") (pin "1") (pinfunction "P_1") (pintype "passive"))
    )
    (net (code "15") (name "Net-(IC1-(PCINT0{slash}AREF{slash}ADC0)PA0)") (class "Default")
      (node (ref "IC1") (pin "13") (pinfunction "(PCINT0/AREF/ADC0)PA0_13") (pintype "bidirectional"))
      (node (ref "R1") (pin "2") (pinfunction "2_2") (pintype "passive"))
      (node (ref "R2") (pin "2") (pinfunction "2_2") (pintype "passive"))
    )
    (net (code "16") (name "Net-(M2-P)") (class "Default")
      (node (ref "M2") (pin "1") (pinfunction "P_1") (pintype "passive"))
      (node (ref "SJ1") (pin "2") (pinfunction "2_2") (pintype "passive"))
    )
    (net (code "17") (name "Net-(M3-P)") (class "Default")
      (node (ref "M3") (pin "1") (pinfunction "P_1") (pintype "passive"))
      (node (ref "SJ2") (pin "2") (pinfunction "2_2") (pintype "passive"))
    )
    (net (code "18") (name "Net-(M4-P)") (class "Default")
      (node (ref "M4") (pin "1") (pinfunction "P_1") (pintype "passive"))
      (node (ref "SJ3") (pin "2") (pinfunction "2_2") (pintype "passive"))
    )
    (net (code "19") (name "RESET") (class "Default")
      (node (ref "5") (pin "1") (pinfunction "P_1") (pintype "passive"))
      (node (ref "IC1") (pin "4") (pinfunction "(PCINT11/RESET/DW)PB3_4") (pintype "bidirectional"))
      (node (ref "RESET") (pin "1") (pinfunction "P_1") (pintype "passive"))
      (node (ref "SV1") (pin "5") (pinfunction "5_5") (pintype "passive"))
    )
    (net (code "20") (name "SCL") (class "Default")
      (node (ref "7") (pin "1") (pinfunction "P_1") (pintype "passive"))
      (node (ref "IC1") (pin "9") (pinfunction "(PCINT4/T1/SCL/USCK/ADC4)PA4_9") (pintype "bidirectional"))
      (node (ref "L_SCL") (pin "1") (pinfunction "P_1") (pintype "passive"))
      (node (ref "MISO41") (pin "1") (pinfunction "P_1") (pintype "passive"))
      (node (ref "SCL") (pin "1") (pinfunction "P_1") (pintype "passive"))
      (node (ref "SV1") (pin "3") (pinfunction "3_3") (pintype "passive"))
      (node (ref "SV2") (pin "2") (pinfunction "2_2") (pintype "passive"))
    )
    (net (code "21") (name "SDA") (class "Default")
      (node (ref "1") (pin "1") (pinfunction "P_1") (pintype "passive"))
      (node (ref "IC1") (pin "7") (pinfunction "(PCINT6/OC1A/SDA/MOSI/ADC6)PA6_7") (pintype "bidirectional"))
      (node (ref "L_SDA") (pin "1") (pinfunction "P_1") (pintype "passive"))
      (node (ref "MISO21") (pin "1") (pinfunction "P_1") (pintype "passive"))
      (node (ref "SDA") (pin "1") (pinfunction "P_1") (pintype "passive"))
      (node (ref "SV1") (pin "4") (pinfunction "4_4") (pintype "passive"))
      (node (ref "SV2") (pin "1") (pinfunction "1_1") (pintype "passive"))
    )
    (net (code "22") (name "U3.3") (class "Default")
      (node (ref "2") (pin "1") (pinfunction "P_1") (pintype "passive"))
      (node (ref "C1") (pin "1") (pinfunction "1_1") (pintype "passive"))
      (node (ref "IC1") (pin "1") (pinfunction "VCC_1") (pintype "power_in"))
      (node (ref "L_VCC") (pin "1") (pinfunction "P_1") (pintype "passive"))
      (node (ref "M10") (pin "1") (pinfunction "P_1") (pintype "passive"))
      (node (ref "MISO22") (pin "1") (pinfunction "P_1") (pintype "passive"))
      (node (ref "MISO23") (pin "1") (pinfunction "P_1") (pintype "passive"))
      (node (ref "MISO24") (pin "1") (pinfunction "P_1") (pintype "passive"))
      (node (ref "MISO25") (pin "1") (pinfunction "P_1") (pintype "passive"))
      (node (ref "MISO26") (pin "1") (pinfunction "P_1") (pintype "passive"))
      (node (ref "MISO27") (pin "1") (pinfunction "P_1") (pintype "passive"))
      (node (ref "MISO28") (pin "1") (pinfunction "P_1") (pintype "passive"))
      (node (ref "MISO29") (pin "1") (pinfunction "P_1") (pintype "passive"))
      (node (ref "MISO30") (pin "1") (pinfunction "P_1") (pintype "passive"))
      (node (ref "MISO31") (pin "1") (pinfunction "P_1") (pintype "passive"))
      (node (ref "MISO32") (pin "1") (pinfunction "P_1") (pintype "passive"))
      (node (ref "MISO33") (pin "1") (pinfunction "P_1") (pintype "passive"))
      (node (ref "MISO34") (pin "1") (pinfunction "P_1") (pintype "passive"))
      (node (ref "MISO35") (pin "1") (pinfunction "P_1") (pintype "passive"))
      (node (ref "MISO36") (pin "1") (pinfunction "P_1") (pintype "passive"))
      (node (ref "MISO37") (pin "1") (pinfunction "P_1") (pintype "passive"))
      (node (ref "MISO4") (pin "1") (pinfunction "P_1") (pintype "passive"))
      (node (ref "SJ1") (pin "1") (pinfunction "1_1") (pintype "passive"))
      (node (ref "SJ2") (pin "1") (pinfunction "1_1") (pintype "passive"))
      (node (ref "SJ3") (pin "1") (pinfunction "1_1") (pintype "passive"))
      (node (ref "SV1") (pin "2") (pinfunction "2_2") (pintype "passive"))
      (node (ref "SV2") (pin "3") (pinfunction "3_3") (pintype "passive"))
      (node (ref "U33") (pin "1") (pinfunction "P_1") (pintype "passive"))
    )
    (net (code "23") (name "U5") (class "Default")
      (node (ref "4") (pin "1") (pinfunction "P_1") (pintype "passive"))
      (node (ref "C2") (pin "+") (pinfunction "+_+") (pintype "passive"))
      (node (ref "M16") (pin "1") (pinfunction "P_1") (pintype "passive"))
      (node (ref "R2") (pin "1") (pinfunction "1_1") (pintype "passive"))
      (node (ref "U5") (pin "1") (pinfunction "P_1") (pintype "passive"))
    )
    (net (code "24") (name "XSHUT") (class "Default")
      (node (ref "IC1") (pin "5") (pinfunction "(PCINT10/INT0/OC0A/CKOUT)PB2_5") (pintype "bidirectional"))
      (node (ref "L_XSHUT") (pin "1") (pinfunction "P_1") (pintype "passive"))
    )
    (net (code "25") (name "unconnected-(PAD1-P-Pad1)") (class "Default")
      (node (ref "PAD1") (pin "1") (pinfunction "P_1") (pintype "passive"))
    )
    (net (code "26") (name "unconnected-(PAD2-P-Pad1)") (class "Default")
      (node (ref "PAD2") (pin "1") (pinfunction "P_1") (pintype "passive"))
    )
    (net (code "27") (name "unconnected-(PAD3-P-Pad1)") (class "Default")
      (node (ref "PAD3") (pin "1") (pinfunction "P_1") (pintype "passive"))
    )
    (net (code "28") (name "unconnected-(PAD4-P-Pad1)") (class "Default")
      (node (ref "PAD4") (pin "1") (pinfunction "P_1") (pintype "passive"))
    )
    (net (code "29") (name "unconnected-(PAD5-P-Pad1)") (class "Default")
      (node (ref "PAD5") (pin "1") (pinfunction "P_1") (pintype "passive"))
    )
    (net (code "30") (name "unconnected-(PAD6-P-Pad1)") (class "Default")
      (node (ref "PAD6") (pin "1") (pinfunction "P_1") (pintype "passive"))
    )
    (net (code "31") (name "unconnected-(PAD7-P-Pad1)") (class "Default")
      (node (ref "PAD7") (pin "1") (pinfunction "P_1") (pintype "passive"))
    )
    (net (code "32") (name "unconnected-(PAD8-P-Pad1)") (class "Default")
      (node (ref "PAD8") (pin "1") (pinfunction "P_1") (pintype "passive"))
    )
    (net (code "33") (name "unconnected-(PAD9-P-Pad1)") (class "Default")
      (node (ref "PAD9") (pin "1") (pinfunction "P_1") (pintype "passive"))
    )
    (net (code "34") (name "unconnected-(PAD10-P-Pad1)") (class "Default")
      (node (ref "PAD10") (pin "1") (pinfunction "P_1") (pintype "passive"))
    )
    (net (code "35") (name "unconnected-(PAD11-P-Pad1)") (class "Default")
      (node (ref "PAD11") (pin "1") (pinfunction "P_1") (pintype "passive"))
    )
    (net (code "36") (name "unconnected-(PAD12-P-Pad1)") (class "Default")
      (node (ref "PAD12") (pin "1") (pinfunction "P_1") (pintype "passive"))
    )
    (net (code "37") (name "unconnected-(PAD13-P-Pad1)") (class "Default")
      (node (ref "PAD13") (pin "1") (pinfunction "P_1") (pintype "passive"))
    )
    (net (code "38") (name "unconnected-(PAD14-P-Pad1)") (class "Default")
      (node (ref "PAD14") (pin "1") (pinfunction "P_1") (pintype "passive"))
    )
    (net (code "39") (name "unconnected-(PAD15-P-Pad1)") (class "Default")
      (node (ref "PAD15") (pin "1") (pinfunction "P_1") (pintype "passive"))
    )
    (net (code "40") (name "unconnected-(PAD16-P-Pad1)") (class "Default")
      (node (ref "PAD16") (pin "1") (pinfunction "P_1") (pintype "passive"))
    )
    (net (code "41") (name "unconnected-(PAD17-P-Pad1)") (class "Default")
      (node (ref "PAD17") (pin "1") (pinfunction "P_1") (pintype "passive"))
    )
    (net (code "42") (name "unconnected-(PAD18-P-Pad1)") (class "Default")
      (node (ref "PAD18") (pin "1") (pinfunction "P_1") (pintype "passive"))
    )
    (net (code "43") (name "unconnected-(PAD19-P-Pad1)") (class "Default")
      (node (ref "PAD19") (pin "1") (pinfunction "P_1") (pintype "passive"))
    )
    (net (code "44") (name "unconnected-(PAD20-P-Pad1)") (class "Default")
      (node (ref "PAD20") (pin "1") (pinfunction "P_1") (pintype "passive"))
    )
    (net (code "45") (name "unconnected-(PAD21-P-Pad1)") (class "Default")
      (node (ref "PAD21") (pin "1") (pinfunction "P_1") (pintype "passive"))
    )
    (net (code "46") (name "unconnected-(PAD22-P-Pad1)") (class "Default")
      (node (ref "PAD22") (pin "1") (pinfunction "P_1") (pintype "passive"))
    )
    (net (code "47") (name "unconnected-(PAD23-P-Pad1)") (class "Default")
      (node (ref "PAD23") (pin "1") (pinfunction "P_1") (pintype "passive"))
    )
    (net (code "48") (name "unconnected-(PAD24-P-Pad1)") (class "Default")
      (node (ref "PAD24") (pin "1") (pinfunction "P_1") (pintype "passive"))
    )
    (net (code "49") (name "unconnected-(PAD25-P-Pad1)") (class "Default")
      (node (ref "PAD25") (pin "1") (pinfunction "P_1") (pintype "passive"))
    )
    (net (code "50") (name "unconnected-(PAD26-P-Pad1)") (class "Default")
      (node (ref "PAD26") (pin "1") (pinfunction "P_1") (pintype "passive"))
    )
    (net (code "51") (name "unconnected-(PAD27-P-Pad1)") (class "Default")
      (node (ref "PAD27") (pin "1") (pinfunction "P_1") (pintype "passive"))
    )
    (net (code "52") (name "unconnected-(PAD28-P-Pad1)") (class "Default")
      (node (ref "PAD28") (pin "1") (pinfunction "P_1") (pintype "passive"))
    )
    (net (code "53") (name "unconnected-(PAD29-P-Pad1)") (class "Default")
      (node (ref "PAD29") (pin "1") (pinfunction "P_1") (pintype "passive"))
    )
    (net (code "54") (name "unconnected-(PAD30-P-Pad1)") (class "Default")
      (node (ref "PAD30") (pin "1") (pinfunction "P_1") (pintype "passive"))
    )
    (net (code "55") (name "unconnected-(PAD31-P-Pad1)") (class "Default")
      (node (ref "PAD31") (pin "1") (pinfunction "P_1") (pintype "passive"))
    )
    (net (code "56") (name "unconnected-(PAD32-P-Pad1)") (class "Default")
      (node (ref "PAD32") (pin "1") (pinfunction "P_1") (pintype "passive"))
    )
    (net (code "57") (name "unconnected-(PAD33-P-Pad1)") (class "Default")
      (node (ref "PAD33") (pin "1") (pinfunction "P_1") (pintype "passive"))
    )
    (net (code "58") (name "unconnected-(PAD34-P-Pad1)") (class "Default")
      (node (ref "PAD34") (pin "1") (pinfunction "P_1") (pintype "passive"))
    )
    (net (code "59") (name "unconnected-(PAD35-P-Pad1)") (class "Default")
      (node (ref "PAD35") (pin "1") (pinfunction "P_1") (pintype "passive"))
    )
    (net (code "60") (name "unconnected-(PAD36-P-Pad1)") (class "Default")
      (node (ref "PAD36") (pin "1") (pinfunction "P_1") (pintype "passive"))
    )
    (net (code "61") (name "unconnected-(PAD37-P-Pad1)") (class "Default")
      (node (ref "PAD37") (pin "1") (pinfunction "P_1") (pintype "passive"))
    )
    (net (code "62") (name "unconnected-(PAD38-P-Pad1)") (class "Default")
      (node (ref "PAD38") (pin "1") (pinfunction "P_1") (pintype "passive"))
    )
    (net (code "63") (name "unconnected-(PAD39-P-Pad1)") (class "Default")
      (node (ref "PAD39") (pin "1") (pinfunction "P_1") (pintype "passive"))
    )
    (net (code "64") (name "unconnected-(PAD40-P-Pad1)") (class "Default")
      (node (ref "PAD40") (pin "1") (pinfunction "P_1") (pintype "passive"))
    )
    (net (code "65") (name "unconnected-(PAD41-P-Pad1)") (class "Default")
      (node (ref "PAD41") (pin "1") (pinfunction "P_1") (pintype "passive"))
    )
    (net (code "66") (name "unconnected-(PAD42-P-Pad1)") (class "Default")
      (node (ref "PAD42") (pin "1") (pinfunction "P_1") (pintype "passive"))
    )
    (net (code "67") (name "unconnected-(PAD43-P-Pad1)") (class "Default")
      (node (ref "PAD43") (pin "1") (pinfunction "P_1") (pintype "passive"))
    )
    (net (code "68") (name "unconnected-(PAD44-P-Pad1)") (class "Default")
      (node (ref "PAD44") (pin "1") (pinfunction "P_1") (pintype "passive"))
    )
    (net (code "69") (name "unconnected-(PAD45-P-Pad1)") (class "Default")
      (node (ref "PAD45") (pin "1") (pinfunction "P_1") (pintype "passive"))
    )
    (net (code "70") (name "unconnected-(PAD46-P-Pad1)") (class "Default")
      (node (ref "PAD46") (pin "1") (pinfunction "P_1") (pintype "passive"))
    )
    (net (code "71") (name "unconnected-(PAD47-P-Pad1)") (class "Default")
      (node (ref "PAD47") (pin "1") (pinfunction "P_1") (pintype "passive"))
    )
    (net (code "72") (name "unconnected-(PAD48-P-Pad1)") (class "Default")
      (node (ref "PAD48") (pin "1") (pinfunction "P_1") (pintype "passive"))
    )
    (net (code "73") (name "unconnected-(PAD49-P-Pad1)") (class "Default")
      (node (ref "PAD49") (pin "1") (pinfunction "P_1") (pintype "passive"))
    )
    (net (code "74") (name "unconnected-(PAD50-P-Pad1)") (class "Default")
      (node (ref "PAD50") (pin "1") (pinfunction "P_1") (pintype "passive"))
    )
    (net (code "75") (name "unconnected-(PAD51-P-Pad1)") (class "Default")
      (node (ref "PAD51") (pin "1") (pinfunction "P_1") (pintype "passive"))
    )
    (net (code "76") (name "unconnected-(PAD52-P-Pad1)") (class "Default")
      (node (ref "PAD52") (pin "1") (pinfunction "P_1") (pintype "passive"))
    )
    (net (code "77") (name "unconnected-(PAD53-P-Pad1)") (class "Default")
      (node (ref "PAD53") (pin "1") (pinfunction "P_1") (pintype "passive"))
    )
    (net (code "78") (name "unconnected-(PAD54-P-Pad1)") (class "Default")
      (node (ref "PAD54") (pin "1") (pinfunction "P_1") (pintype "passive"))
    )
    (net (code "79") (name "unconnected-(PAD55-P-Pad1)") (class "Default")
      (node (ref "PAD55") (pin "1") (pinfunction "P_1") (pintype "passive"))
    )
    (net (code "80") (name "unconnected-(PAD56-P-Pad1)") (class "Default")
      (node (ref "PAD56") (pin "1") (pinfunction "P_1") (pintype "passive"))
    )
    (net (code "81") (name "unconnected-(PAD57-P-Pad1)") (class "Default")
      (node (ref "PAD57") (pin "1") (pinfunction "P_1") (pintype "passive"))
    )
    (net (code "82") (name "unconnected-(PAD58-P-Pad1)") (class "Default")
      (node (ref "PAD58") (pin "1") (pinfunction "P_1") (pintype "passive"))
    )
    (net (code "83") (name "unconnected-(PAD59-P-Pad1)") (class "Default")
      (node (ref "PAD59") (pin "1") (pinfunction "P_1") (pintype "passive"))
    )
    (net (code "84") (name "unconnected-(PAD60-P-Pad1)") (class "Default")
      (node (ref "PAD60") (pin "1") (pinfunction "P_1") (pintype "passive"))
    )
    (net (code "85") (name "unconnected-(PAD61-P-Pad1)") (class "Default")
      (node (ref "PAD61") (pin "1") (pinfunction "P_1") (pintype "passive"))
    )
    (net (code "86") (name "unconnected-(PAD62-P-Pad1)") (class "Default")
      (node (ref "PAD62") (pin "1") (pinfunction "P_1") (pintype "passive"))
    )
    (net (code "87") (name "unconnected-(PAD63-P-Pad1)") (class "Default")
      (node (ref "PAD63") (pin "1") (pinfunction "P_1") (pintype "passive"))
    )
    (net (code "88") (name "unconnected-(PAD64-P-Pad1)") (class "Default")
      (node (ref "PAD64") (pin "1") (pinfunction "P_1") (pintype "passive"))
    )
    (net (code "89") (name "unconnected-(PAD65-P-Pad1)") (class "Default")
      (node (ref "PAD65") (pin "1") (pinfunction "P_1") (pintype "passive"))
    )
    (net (code "90") (name "unconnected-(PAD66-P-Pad1)") (class "Default")
      (node (ref "PAD66") (pin "1") (pinfunction "P_1") (pintype "passive"))
    )
    (net (code "91") (name "unconnected-(PAD67-P-Pad1)") (class "Default")
      (node (ref "PAD67") (pin "1") (pinfunction "P_1") (pintype "passive"))
    )
    (net (code "92") (name "unconnected-(PAD68-P-Pad1)") (class "Default")
      (node (ref "PAD68") (pin "1") (pinfunction "P_1") (pintype "passive"))
    )
    (net (code "93") (name "unconnected-(PAD69-P-Pad1)") (class "Default")
      (node (ref "PAD69") (pin "1") (pinfunction "P_1") (pintype "passive"))
    )
    (net (code "94") (name "unconnected-(PAD70-P-Pad1)") (class "Default")
      (node (ref "PAD70") (pin "1") (pinfunction "P_1") (pintype "passive"))
    )
    (net (code "95") (name "unconnected-(PAD71-P-Pad1)") (class "Default")
      (node (ref "PAD71") (pin "1") (pinfunction "P_1") (pintype "passive"))
    )
    (net (code "96") (name "unconnected-(PAD72-P-Pad1)") (class "Default")
      (node (ref "PAD72") (pin "1") (pinfunction "P_1") (pintype "passive"))
    )
    (net (code "97") (name "unconnected-(PAD73-P-Pad1)") (class "Default")
      (node (ref "PAD73") (pin "1") (pinfunction "P_1") (pintype "passive"))
    )
    (net (code "98") (name "unconnected-(PAD74-P-Pad1)") (class "Default")
      (node (ref "PAD74") (pin "1") (pinfunction "P_1") (pintype "passive"))
    )
    (net (code "99") (name "unconnected-(PAD75-P-Pad1)") (class "Default")
      (node (ref "PAD75") (pin "1") (pinfunction "P_1") (pintype "passive"))
    )
    (net (code "100") (name "unconnected-(PAD76-P-Pad1)") (class "Default")
      (node (ref "PAD76") (pin "1") (pinfunction "P_1") (pintype "passive"))
    )
    (net (code "101") (name "unconnected-(PAD77-P-Pad1)") (class "Default")
      (node (ref "PAD77") (pin "1") (pinfunction "P_1") (pintype "passive"))
    )
    (net (code "102") (name "unconnected-(PAD78-P-Pad1)") (class "Default")
      (node (ref "PAD78") (pin "1") (pinfunction "P_1") (pintype "passive"))
    )
    (net (code "103") (name "unconnected-(PAD79-P-Pad1)") (class "Default")
      (node (ref "PAD79") (pin "1") (pinfunction "P_1") (pintype "passive"))
    )
    (net (code "104") (name "unconnected-(PAD80-P-Pad1)") (class "Default")
      (node (ref "PAD80") (pin "1") (pinfunction "P_1") (pintype "passive"))
    )
    (net (code "105") (name "unconnected-(PAD81-P-Pad1)") (class "Default")
      (node (ref "PAD81") (pin "1") (pinfunction "P_1") (pintype "passive"))
    )
    (net (code "106") (name "unconnected-(PAD82-P-Pad1)") (class "Default")
      (node (ref "PAD82") (pin "1") (pinfunction "P_1") (pintype "passive"))
    )
    (net (code "107") (name "unconnected-(PAD83-P-Pad1)") (class "Default")
      (node (ref "PAD83") (pin "1") (pinfunction "P_1") (pintype "passive"))
    )
    (net (code "108") (name "unconnected-(PAD84-P-Pad1)") (class "Default")
      (node (ref "PAD84") (pin "1") (pinfunction "P_1") (pintype "passive"))
    )
    (net (code "109") (name "unconnected-(PAD85-P-Pad1)") (class "Default")
      (node (ref "PAD85") (pin "1") (pinfunction "P_1") (pintype "passive"))
    )
    (net (code "110") (name "unconnected-(PAD86-P-Pad1)") (class "Default")
      (node (ref "PAD86") (pin "1") (pinfunction "P_1") (pintype "passive"))
    )
    (net (code "111") (name "unconnected-(PAD87-P-Pad1)") (class "Default")
      (node (ref "PAD87") (pin "1") (pinfunction "P_1") (pintype "passive"))
    )
    (net (code "112") (name "unconnected-(PAD88-P-Pad1)") (class "Default")
      (node (ref "PAD88") (pin "1") (pinfunction "P_1") (pintype "passive"))
    )
    (net (code "113") (name "unconnected-(PAD89-P-Pad1)") (class "Default")
      (node (ref "PAD89") (pin "1") (pinfunction "P_1") (pintype "passive"))
    )
    (net (code "114") (name "unconnected-(PAD90-P-Pad1)") (class "Default")
      (node (ref "PAD90") (pin "1") (pinfunction "P_1") (pintype "passive"))
    )
    (net (code "115") (name "unconnected-(PAD91-P-Pad1)") (class "Default")
      (node (ref "PAD91") (pin "1") (pinfunction "P_1") (pintype "passive"))
    )
    (net (code "116") (name "unconnected-(PAD92-P-Pad1)") (class "Default")
      (node (ref "PAD92") (pin "1") (pinfunction "P_1") (pintype "passive"))
    )
    (net (code "117") (name "unconnected-(PAD93-P-Pad1)") (class "Default")
      (node (ref "PAD93") (pin "1") (pinfunction "P_1") (pintype "passive"))
    )
    (net (code "118") (name "unconnected-(PAD94-P-Pad1)") (class "Default")
      (node (ref "PAD94") (pin "1") (pinfunction "P_1") (pintype "passive"))
    )
    (net (code "119") (name "unconnected-(PAD95-P-Pad1)") (class "Default")
      (node (ref "PAD95") (pin "1") (pinfunction "P_1") (pintype "passive"))
    )
    (net (code "120") (name "unconnected-(PAD96-P-Pad1)") (class "Default")
      (node (ref "PAD96") (pin "1") (pinfunction "P_1") (pintype "passive"))
    )
  )
)
